# Microcontroller.net
KiCad netlist of a schematic drawn in Altium Designer
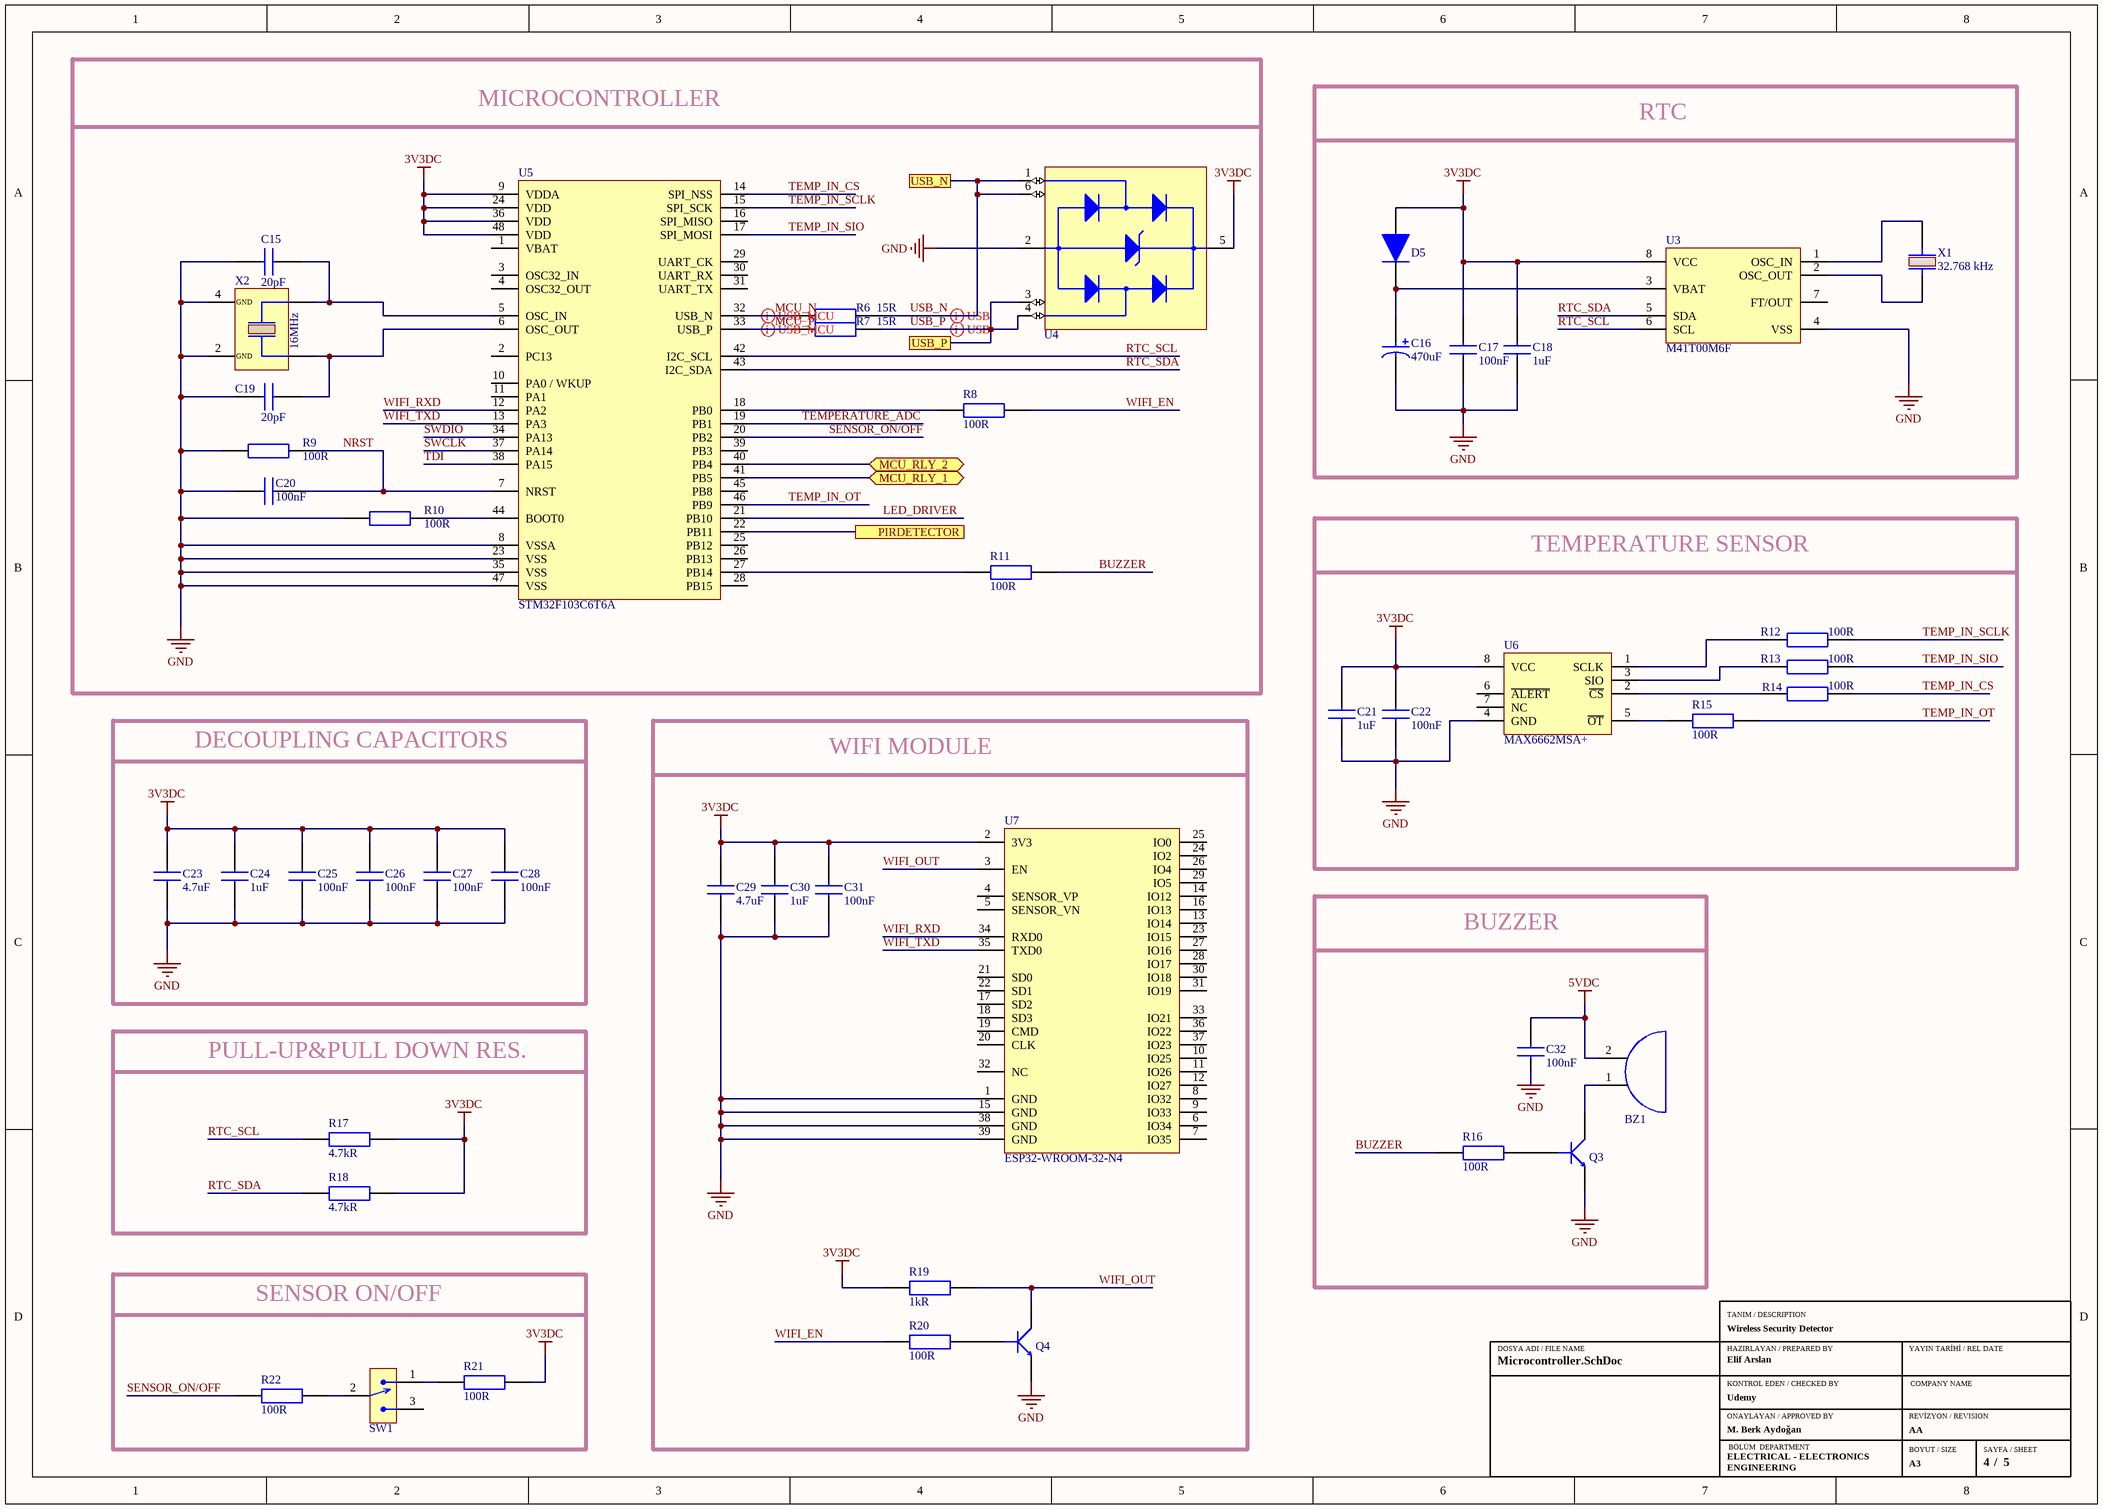
[diagram p0: Microcontroller.SchDoc]

(export (version "E")
  (design (tool "Eeschema 10.0.6"))
  (components
    (comp (ref "BZ1")
      (value "CMI-9605IC-0580T")
      (footprint "CMI-9605IC")
      (description "Audio Buzzer Magnetic 3VDC 7VDC 30mA 5VDC 85dB 2600Hz to 2800Hz Through Hole Pin Box")
      (fields (field (name "MANUFACTURER") "CUI Devices"))
      (libsource (lib "UDEMY_Library") (part "CMI-9605IC-0580T"))
    )
    (comp (ref "C15")
      (value "CL10C200JB8NNNC")
      (footprint "CAP_0603")
      (description "CAP CER 20pF %5 0603")
      (fields
        (field (name "MANUFACTURER") "Samsung")
        (field (name "TOLERANCE") "5%")
        (field (name "CAPACITANCE") "20pF")
      )
      (libsource (lib "UDEMY_Library") (part "CAP CER 20pF 0603"))
    )
    (comp (ref "C16")
      (value "ESH477M050AL3AA")
      (footprint "CAP_RADIAL_D10_P5")
      (description "CAP ALUM 470UF 20% 50V RADIAL")
      (fields
        (field (name "MANUFACTURER") "KEMET")
        (field (name "TOLERANCE") "20%")
        (field (name "CAPACITANCE") "470uF")
      )
      (libsource (lib "UDEMY_Library") (part "CAP ALU ELEC 470uF 50V"))
    )
    (comp (ref "C17")
      (value "CL21B104KBCNNNC")
      (footprint "CAP_0805")
      (description "CAP CER 0.1UF  %10 50V X7R  0805")
      (fields
        (field (name "MANUFACTURER") "Samsung")
        (field (name "TOLERANCE") "10%")
        (field (name "CAPACITANCE") "100nF")
      )
      (libsource (lib "UDEMY_Library") (part "CAP CER 100nF 0805"))
    )
    (comp (ref "C18")
      (value "CL21B105KBFNNNE")
      (footprint "CAP_0805")
      (description "CAP CER 1UF %10 50V 0805")
      (fields
        (field (name "MANUFACTURER") "Samsung")
        (field (name "TOLERANCE") "10%")
        (field (name "CAPACITANCE") "1uF")
      )
      (libsource (lib "UDEMY_Library") (part "CAP CER 1uF 0805"))
    )
    (comp (ref "C19")
      (value "CL10C200JB8NNNC")
      (footprint "CAP_0603")
      (description "CAP CER 20pF %5 0603")
      (fields
        (field (name "MANUFACTURER") "Samsung")
        (field (name "TOLERANCE") "5%")
        (field (name "CAPACITANCE") "20pF")
      )
      (libsource (lib "UDEMY_Library") (part "CAP CER 20pF 0603"))
    )
    (comp (ref "C20")
      (value "C0603C104K4RACTU")
      (footprint "CAP_0603")
      (description "CAP CER 100nF %10 0603 SMD")
      (fields
        (field (name "MANUFACTURER") "KEMET")
        (field (name "TOLERANCE") "10%")
        (field (name "CAPACITANCE") "100nF")
      )
      (libsource (lib "UDEMY_Library") (part "CAP CER 100nF 0603"))
    )
    (comp (ref "C21")
      (value "CL21B105KBFNNNE")
      (footprint "CAP_0805")
      (description "CAP CER 1UF %10 50V 0805")
      (fields
        (field (name "MANUFACTURER") "Samsung")
        (field (name "TOLERANCE") "10%")
        (field (name "CAPACITANCE") "1uF")
      )
      (libsource (lib "UDEMY_Library") (part "CAP CER 1uF 0805"))
    )
    (comp (ref "C22")
      (value "CL21B104KBCNNNC")
      (footprint "CAP_0805")
      (description "CAP CER 0.1UF  %10 50V X7R  0805")
      (fields
        (field (name "MANUFACTURER") "Samsung")
        (field (name "TOLERANCE") "10%")
        (field (name "CAPACITANCE") "100nF")
      )
      (libsource (lib "UDEMY_Library") (part "CAP CER 100nF 0805"))
    )
    (comp (ref "C23")
      (value "CL21A475KAQNNNE")
      (footprint "CAP_0805")
      (description "CAP CER 4.7UF 25V X5R %10 0805")
      (fields
        (field (name "MANUFACTURER") "Samsung")
        (field (name "TOLERANCE") "10%")
        (field (name "CAPACITANCE") "4.7uF")
      )
      (libsource (lib "UDEMY_Library") (part "CAP CER  4.7uF 0805"))
    )
    (comp (ref "C24")
      (value "CL21B105KBFNNNE")
      (footprint "CAP_0805")
      (description "CAP CER 1UF %10 50V 0805")
      (fields
        (field (name "MANUFACTURER") "Samsung")
        (field (name "TOLERANCE") "10%")
        (field (name "CAPACITANCE") "1uF")
      )
      (libsource (lib "UDEMY_Library") (part "CAP CER 1uF 0805"))
    )
    (comp (ref "C25")
      (value "C0603C104K4RACTU")
      (footprint "CAP_0603")
      (description "CAP CER 100nF %10 0603 SMD")
      (fields
        (field (name "MANUFACTURER") "KEMET")
        (field (name "TOLERANCE") "10%")
        (field (name "CAPACITANCE") "100nF")
      )
      (libsource (lib "UDEMY_Library") (part "CAP CER 100nF 0603"))
    )
    (comp (ref "C26")
      (value "C0603C104K4RACTU")
      (footprint "CAP_0603")
      (description "CAP CER 100nF %10 0603 SMD")
      (fields
        (field (name "MANUFACTURER") "KEMET")
        (field (name "TOLERANCE") "10%")
        (field (name "CAPACITANCE") "100nF")
      )
      (libsource (lib "UDEMY_Library") (part "CAP CER 100nF 0603"))
    )
    (comp (ref "C27")
      (value "C0603C104K4RACTU")
      (footprint "CAP_0603")
      (description "CAP CER 100nF %10 0603 SMD")
      (fields
        (field (name "MANUFACTURER") "KEMET")
        (field (name "TOLERANCE") "10%")
        (field (name "CAPACITANCE") "100nF")
      )
      (libsource (lib "UDEMY_Library") (part "CAP CER 100nF 0603"))
    )
    (comp (ref "C28")
      (value "C0603C104K4RACTU")
      (footprint "CAP_0603")
      (description "CAP CER 100nF %10 0603 SMD")
      (fields
        (field (name "MANUFACTURER") "KEMET")
        (field (name "TOLERANCE") "10%")
        (field (name "CAPACITANCE") "100nF")
      )
      (libsource (lib "UDEMY_Library") (part "CAP CER 100nF 0603"))
    )
    (comp (ref "C29")
      (value "CL21A475KAQNNNE")
      (footprint "CAP_0805")
      (description "CAP CER 4.7UF 25V X5R %10 0805")
      (fields
        (field (name "MANUFACTURER") "Samsung")
        (field (name "TOLERANCE") "10%")
        (field (name "CAPACITANCE") "4.7uF")
      )
      (libsource (lib "UDEMY_Library") (part "CAP CER  4.7uF 0805"))
    )
    (comp (ref "C30")
      (value "CL21B105KBFNNNE")
      (footprint "CAP_0805")
      (description "CAP CER 1UF %10 50V 0805")
      (fields
        (field (name "MANUFACTURER") "Samsung")
        (field (name "TOLERANCE") "10%")
        (field (name "CAPACITANCE") "1uF")
      )
      (libsource (lib "UDEMY_Library") (part "CAP CER 1uF 0805"))
    )
    (comp (ref "C31")
      (value "CL21B104KBCNNNC")
      (footprint "CAP_0805")
      (description "CAP CER 0.1UF  %10 50V X7R  0805")
      (fields
        (field (name "MANUFACTURER") "Samsung")
        (field (name "TOLERANCE") "10%")
        (field (name "CAPACITANCE") "100nF")
      )
      (libsource (lib "UDEMY_Library") (part "CAP CER 100nF 0805"))
    )
    (comp (ref "C32")
      (value "CL21B104KBCNNNC")
      (footprint "CAP_0805")
      (description "CAP CER 0.1UF  %10 50V X7R  0805")
      (fields
        (field (name "MANUFACTURER") "Samsung")
        (field (name "TOLERANCE") "10%")
        (field (name "CAPACITANCE") "100nF")
      )
      (libsource (lib "UDEMY_Library") (part "CAP CER 100nF 0805"))
    )
    (comp (ref "D5")
      (value "1N4148WS")
      (footprint "SOD323F")
      (description "VR=75V IF=150mA Trr=4ns P=200mW")
      (fields (field (name "MANUFACTURER") "ON Semiconductor / Fairchild"))
      (libsource (lib "UDEMY_Library") (part "1N4148WS"))
    )
    (comp (ref "Q3")
      (value "MMBT3904-7-F")
      (footprint "SOT-23F")
      (description "Bipolar (BJT) Transistor NPN 40 V 200 mA 300MHz 300 mW Surface Mount SOT-23-3")
      (fields (field (name "MANUFACTURER") "Diodes Zetex"))
      (libsource (lib "UDEMY_Library") (part "MMBT3904-7-F"))
    )
    (comp (ref "Q4")
      (value "MMBT3904-7-F")
      (footprint "SOT-23F")
      (description "Bipolar (BJT) Transistor NPN 40 V 200 mA 300MHz 300 mW Surface Mount SOT-23-3")
      (fields (field (name "MANUFACTURER") "Diodes Zetex"))
      (libsource (lib "UDEMY_Library") (part "MMBT3904-7-F"))
    )
    (comp (ref "R6")
      (value "RC0603JR-0715RL")
      (footprint "RES_0603")
      (description "RES 15 %5 OHM 0603 SMD")
      (fields
        (field (name "MANUFACTURER") "Yageo")
        (field (name "TOLERANCE") "5%")
        (field (name "RESISTANCE") "15R")
      )
      (libsource (lib "UDEMY_Library") (part "RES 15 OHM 0603"))
    )
    (comp (ref "R7")
      (value "RC0603JR-0715RL")
      (footprint "RES_0603")
      (description "RES 15 %5 OHM 0603 SMD")
      (fields
        (field (name "MANUFACTURER") "Yageo")
        (field (name "TOLERANCE") "5%")
        (field (name "RESISTANCE") "15R")
      )
      (libsource (lib "UDEMY_Library") (part "RES 15 OHM 0603"))
    )
    (comp (ref "R8")
      (value "RC0603JR-07100RL")
      (footprint "RES_0603")
      (description "RES 100 %5 OHM 0603 SMD")
      (fields
        (field (name "MANUFACTURER") "Yageo")
        (field (name "TOLERANCE") "5%")
        (field (name "RESISTANCE") "100R")
      )
      (libsource (lib "UDEMY_Library") (part "RES 100 OHM 0603"))
    )
    (comp (ref "R9")
      (value "RC0603JR-07100RL")
      (footprint "RES_0603")
      (description "RES 100 %5 OHM 0603 SMD")
      (fields
        (field (name "MANUFACTURER") "Yageo")
        (field (name "TOLERANCE") "5%")
        (field (name "RESISTANCE") "100R")
      )
      (libsource (lib "UDEMY_Library") (part "RES 100 OHM 0603"))
    )
    (comp (ref "R10")
      (value "RC0603JR-07100RL")
      (footprint "RES_0603")
      (description "RES 100 %5 OHM 0603 SMD")
      (fields
        (field (name "MANUFACTURER") "Yageo")
        (field (name "TOLERANCE") "5%")
        (field (name "RESISTANCE") "100R")
      )
      (libsource (lib "UDEMY_Library") (part "RES 100 OHM 0603"))
    )
    (comp (ref "R11")
      (value "RC0603JR-07100RL")
      (footprint "RES_0603")
      (description "RES 100 %5 OHM 0603 SMD")
      (fields
        (field (name "MANUFACTURER") "Yageo")
        (field (name "TOLERANCE") "5%")
        (field (name "RESISTANCE") "100R")
      )
      (libsource (lib "UDEMY_Library") (part "RES 100 OHM 0603"))
    )
    (comp (ref "R12")
      (value "RC0603JR-07100RL")
      (footprint "RES_0603")
      (description "RES 100 %5 OHM 0603 SMD")
      (fields
        (field (name "MANUFACTURER") "Yageo")
        (field (name "TOLERANCE") "5%")
        (field (name "RESISTANCE") "100R")
      )
      (libsource (lib "UDEMY_Library") (part "RES 100 OHM 0603"))
    )
    (comp (ref "R13")
      (value "RC0603JR-07100RL")
      (footprint "RES_0603")
      (description "RES 100 %5 OHM 0603 SMD")
      (fields
        (field (name "MANUFACTURER") "Yageo")
        (field (name "TOLERANCE") "5%")
        (field (name "RESISTANCE") "100R")
      )
      (libsource (lib "UDEMY_Library") (part "RES 100 OHM 0603"))
    )
    (comp (ref "R14")
      (value "RC0603JR-07100RL")
      (footprint "RES_0603")
      (description "RES 100 %5 OHM 0603 SMD")
      (fields
        (field (name "MANUFACTURER") "Yageo")
        (field (name "TOLERANCE") "5%")
        (field (name "RESISTANCE") "100R")
      )
      (libsource (lib "UDEMY_Library") (part "RES 100 OHM 0603"))
    )
    (comp (ref "R15")
      (value "RC0603JR-07100RL")
      (footprint "RES_0603")
      (description "RES 100 %5 OHM 0603 SMD")
      (fields
        (field (name "MANUFACTURER") "Yageo")
        (field (name "TOLERANCE") "5%")
        (field (name "RESISTANCE") "100R")
      )
      (libsource (lib "UDEMY_Library") (part "RES 100 OHM 0603"))
    )
    (comp (ref "R16")
      (value "RC0603JR-07100RL")
      (footprint "RES_0603")
      (description "RES 100 %5 OHM 0603 SMD")
      (fields
        (field (name "MANUFACTURER") "Yageo")
        (field (name "TOLERANCE") "5%")
        (field (name "RESISTANCE") "100R")
      )
      (libsource (lib "UDEMY_Library") (part "RES 100 OHM 0603"))
    )
    (comp (ref "R17")
      (value "RC0603JR-074K7L")
      (footprint "RES_0603")
      (description "RES 4.7K OHM %5 0603 SMD")
      (fields
        (field (name "MANUFACTURER") "Yageo")
        (field (name "TOLERANCE") "5%")
        (field (name "RESISTANCE") "4.7kR")
      )
      (libsource (lib "UDEMY_Library") (part "RES 4.7K OHM 0603"))
    )
    (comp (ref "R18")
      (value "RC0603JR-074K7L")
      (footprint "RES_0603")
      (description "RES 4.7K OHM %5 0603 SMD")
      (fields
        (field (name "MANUFACTURER") "Yageo")
        (field (name "TOLERANCE") "5%")
        (field (name "RESISTANCE") "4.7kR")
      )
      (libsource (lib "UDEMY_Library") (part "RES 4.7K OHM 0603"))
    )
    (comp (ref "R19")
      (value "RC0603FR-071KL")
      (footprint "RES_0603")
      (description "RES SMD 1K OHM %1 0603")
      (fields
        (field (name "MANUFACTURER") "Yageo")
        (field (name "TOLERANCE") "1%")
        (field (name "RESISTANCE") "1kR")
      )
      (libsource (lib "UDEMY_Library") (part "RES 1K OHM 0603"))
    )
    (comp (ref "R20")
      (value "RC0603JR-07100RL")
      (footprint "RES_0603")
      (description "RES 100 %5 OHM 0603 SMD")
      (fields
        (field (name "MANUFACTURER") "Yageo")
        (field (name "TOLERANCE") "5%")
        (field (name "RESISTANCE") "100R")
      )
      (libsource (lib "UDEMY_Library") (part "RES 100 OHM 0603"))
    )
    (comp (ref "R21")
      (value "RC0603JR-07100RL")
      (footprint "RES_0603")
      (description "RES 100 %5 OHM 0603 SMD")
      (fields
        (field (name "MANUFACTURER") "Yageo")
        (field (name "TOLERANCE") "5%")
        (field (name "RESISTANCE") "100R")
      )
      (libsource (lib "UDEMY_Library") (part "RES 100 OHM 0603"))
    )
    (comp (ref "R22")
      (value "RC0603JR-07100RL")
      (footprint "RES_0603")
      (description "RES 100 %5 OHM 0603 SMD")
      (fields
        (field (name "MANUFACTURER") "Yageo")
        (field (name "TOLERANCE") "5%")
        (field (name "RESISTANCE") "100R")
      )
      (libsource (lib "UDEMY_Library") (part "RES 100 OHM 0603"))
    )
    (comp (ref "SW1")
      (value "EG1215AA")
      (footprint "EG1215AA")
      (description "Slide Switch, SPDT, 0.025A, 24V, SMD")
      (fields (field (name "MANUFACTURER") "E-Switch") (field (name "TOLERANCE") "4.95%"))
      (libsource (lib "UDEMY_Library") (part "EG1215AA"))
    )
    (comp (ref "U3")
      (value "M41T00M6F")
      (footprint "SOIC8")
      (description "IC RTC CLK/CALENDAR I2C 8-SOIC")
      (fields (field (name "MANUFACTURER") "STMicroelectronics"))
      (libsource (lib "UDEMY_Library") (part "M41T00"))
    )
    (comp (ref "U4")
      (value "USBLC6-2SC6")
      (footprint "SOT-23-6L")
      (description "TVS DIODE 5.25VWM 17VC SOT23-6")
      (fields (field (name "MANUFACTURER") "STMicroelectronics"))
      (libsource (lib "UDEMY_Library") (part "USB PROTECTION"))
    )
    (comp (ref "U5")
      (value "STM32F103C6T6A")
      (footprint "LQFP-48")
      (description "MCU 32-bit STM32F ARM Cortex M3 RISC 32KB Flash 2.5V/3.3V 48-Pin LQFP Tray")
      (fields (field (name "MANUFACTURER") "STMicroelectronics") (field (name "DESIGNED BY") "ELİF"))
      (libsource (lib "UDEMY_Library") (part "STM32F103C6T6A"))
    )
    (comp (ref "U6")
      (value "MAX6662MSA+")
      (footprint "SOIC8")
      (description "Temp Sensor Digital Serial (3-Wire, SPI) 8-Pin SOIC N Tube")
      (fields (field (name "MANUFACTURER") "Maxim"))
      (libsource (lib "UDEMY_Library") (part "MAX6662"))
    )
    (comp (ref "U7")
      (value "ESP32-WROOM-32-N4")
      (footprint "ESP32-32E")
      (description "Rx Txrx Mod Wifi Surface Mount")
      (fields (field (name "MANUFACTURER") "Espressif Systems"))
      (libsource (lib "UDEMY_Library") (part "ESP32-WROOM-32-N4"))
    )
    (comp (ref "X1")
      (value "ABS05-32.768KHZ-T")
      (footprint "ABS05")
      (description "Crystal, 32.768 kHz, SMD, 1.6mm x 1mm, 12.5 pF, 20 ppm, ABS05 Series")
      (fields
        (field (name "MANUFACTURER") "Abracon")
        (field (name "TOLERANCE") "20ppm")
        (field (name "OPERATING FREQUENCY") "32.768 kHz")
      )
      (libsource (lib "UDEMY_Library") (part "CRYSTAL 32758kHZ"))
    )
    (comp (ref "X2")
      (value "ECS-160-20-30B-TR")
      (footprint "ECS")
      (description "16 MHz ±30ppm Crystal 20pF 50 Ohms 4-SMD, No Lead")
      (fields
        (field (name "MANUFACTURER") "ECS International")
        (field (name "TOLERANCE") "50ppm")
        (field (name "FREQUENCY") "16MHz")
      )
      (libsource (lib "UDEMY_Library") (part "CRYSTAL 16MHZ"))
    )
  )
  (nets
    (net (code "1") (name "/BUZZER") (class "Default")
      (node (ref "R11") (pin "2") (pinfunction "2_2") (pintype "passive"))
      (node (ref "R16") (pin "1") (pinfunction "1_1") (pintype "passive"))
    )
    (net (code "2") (name "/LED_DRIVER") (class "Default")
      (node (ref "U5") (pin "21") (pinfunction "PB10_21") (pintype "passive"))
    )
    (net (code "3") (name "/MCU_N") (class "Default")
      (node (ref "R6") (pin "1") (pinfunction "1_1") (pintype "passive"))
      (node (ref "U5") (pin "32") (pinfunction "USB_N_32") (pintype "passive"))
    )
    (net (code "4") (name "/MCU_P") (class "Default")
      (node (ref "R7") (pin "1") (pinfunction "1_1") (pintype "passive"))
      (node (ref "U5") (pin "33") (pinfunction "USB_P_33") (pintype "passive"))
    )
    (net (code "5") (name "/MCU_RLY_1") (class "Default")
      (node (ref "U5") (pin "41") (pinfunction "PB5_41") (pintype "passive"))
    )
    (net (code "6") (name "/MCU_RLY_2") (class "Default")
      (node (ref "U5") (pin "40") (pinfunction "PB4_40") (pintype "passive"))
    )
    (net (code "7") (name "/NRST") (class "Default")
      (node (ref "C20") (pin "1") (pinfunction "1_1") (pintype "passive"))
      (node (ref "R9") (pin "2") (pinfunction "2_2") (pintype "passive"))
      (node (ref "U5") (pin "7") (pinfunction "NRST_7") (pintype "passive"))
    )
    (net (code "8") (name "/PIRDETECTOR") (class "Default")
      (node (ref "U5") (pin "22") (pinfunction "PB11_22") (pintype "passive"))
    )
    (net (code "9") (name "/RTC_SCL") (class "Default")
      (node (ref "R17") (pin "1") (pinfunction "1_1") (pintype "passive"))
      (node (ref "U3") (pin "6") (pinfunction "SCL_6") (pintype "passive"))
      (node (ref "U5") (pin "42") (pinfunction "I2C_SCL_42") (pintype "passive"))
    )
    (net (code "10") (name "/RTC_SDA") (class "Default")
      (node (ref "R18") (pin "1") (pinfunction "1_1") (pintype "passive"))
      (node (ref "U3") (pin "5") (pinfunction "SDA_5") (pintype "passive"))
      (node (ref "U5") (pin "43") (pinfunction "I2C_SDA_43") (pintype "passive"))
    )
    (net (code "11") (name "/SENSOR_ON{slash}OFF") (class "Default")
      (node (ref "R22") (pin "2") (pinfunction "2_2") (pintype "passive"))
      (node (ref "U5") (pin "20") (pinfunction "PB2_20") (pintype "passive"))
    )
    (net (code "12") (name "/SWCLK") (class "Default")
      (node (ref "U5") (pin "37") (pinfunction "PA14_37") (pintype "passive"))
    )
    (net (code "13") (name "/SWDIO") (class "Default")
      (node (ref "U5") (pin "34") (pinfunction "PA13_34") (pintype "passive"))
    )
    (net (code "14") (name "/TDI") (class "Default")
      (node (ref "U5") (pin "38") (pinfunction "PA15_38") (pintype "passive"))
    )
    (net (code "15") (name "/TEMPERATURE_ADC") (class "Default")
      (node (ref "U5") (pin "19") (pinfunction "PB1_19") (pintype "passive"))
    )
    (net (code "16") (name "/TEMP_IN_CS") (class "Default")
      (node (ref "R14") (pin "2") (pinfunction "2_2") (pintype "passive"))
      (node (ref "U5") (pin "14") (pinfunction "SPI_NSS_14") (pintype "passive"))
    )
    (net (code "17") (name "/TEMP_IN_OT") (class "Default")
      (node (ref "R15") (pin "2") (pinfunction "2_2") (pintype "passive"))
      (node (ref "U5") (pin "46") (pinfunction "PB9_46") (pintype "passive"))
    )
    (net (code "18") (name "/TEMP_IN_SCLK") (class "Default")
      (node (ref "R12") (pin "2") (pinfunction "2_2") (pintype "passive"))
      (node (ref "U5") (pin "15") (pinfunction "SPI_SCK_15") (pintype "passive"))
    )
    (net (code "19") (name "/TEMP_IN_SIO") (class "Default")
      (node (ref "R13") (pin "2") (pinfunction "2_2") (pintype "passive"))
      (node (ref "U5") (pin "17") (pinfunction "SPI_MOSI_17") (pintype "passive"))
    )
    (net (code "20") (name "/USB_N") (class "Default")
      (node (ref "R6") (pin "2") (pinfunction "2_2") (pintype "passive"))
      (node (ref "U4") (pin "1") (pinfunction "I/O1_IN_1") (pintype "bidirectional"))
      (node (ref "U4") (pin "6") (pinfunction "I/O1_OUT_6") (pintype "bidirectional"))
    )
    (net (code "21") (name "/USB_P") (class "Default")
      (node (ref "R7") (pin "2") (pinfunction "2_2") (pintype "passive"))
      (node (ref "U4") (pin "3") (pinfunction "I/O2_IN_3") (pintype "bidirectional"))
      (node (ref "U4") (pin "4") (pinfunction "I/O2_OUT_4") (pintype "bidirectional"))
    )
    (net (code "22") (name "/WIFI_EN") (class "Default")
      (node (ref "R20") (pin "1") (pinfunction "1_1") (pintype "passive"))
      (node (ref "R8") (pin "2") (pinfunction "2_2") (pintype "passive"))
    )
    (net (code "23") (name "/WIFI_OUT") (class "Default")
      (node (ref "Q4") (pin "3") (pinfunction "C_3") (pintype "passive"))
      (node (ref "R19") (pin "2") (pinfunction "2_2") (pintype "passive"))
      (node (ref "U7") (pin "3") (pinfunction "EN_3") (pintype "passive"))
    )
    (net (code "24") (name "/WIFI_RXD") (class "Default")
      (node (ref "U5") (pin "12") (pinfunction "PA2_12") (pintype "passive"))
      (node (ref "U7") (pin "34") (pinfunction "RXD0_34") (pintype "passive"))
    )
    (net (code "25") (name "/WIFI_TXD") (class "Default")
      (node (ref "U5") (pin "13") (pinfunction "PA3_13") (pintype "passive"))
      (node (ref "U7") (pin "35") (pinfunction "TXD0_35") (pintype "passive"))
    )
    (net (code "26") (name "3V3DC") (class "Default")
      (node (ref "C17") (pin "2") (pinfunction "2_2") (pintype "passive"))
      (node (ref "C18") (pin "2") (pinfunction "2_2") (pintype "passive"))
      (node (ref "C21") (pin "2") (pinfunction "2_2") (pintype "passive"))
      (node (ref "C22") (pin "2") (pinfunction "2_2") (pintype "passive"))
      (node (ref "C23") (pin "2") (pinfunction "2_2") (pintype "passive"))
      (node (ref "C24") (pin "2") (pinfunction "2_2") (pintype "passive"))
      (node (ref "C25") (pin "2") (pinfunction "2_2") (pintype "passive"))
      (node (ref "C26") (pin "2") (pinfunction "2_2") (pintype "passive"))
      (node (ref "C27") (pin "2") (pinfunction "2_2") (pintype "passive"))
      (node (ref "C28") (pin "2") (pinfunction "2_2") (pintype "passive"))
      (node (ref "C29") (pin "2") (pinfunction "2_2") (pintype "passive"))
      (node (ref "C30") (pin "2") (pinfunction "2_2") (pintype "passive"))
      (node (ref "C31") (pin "2") (pinfunction "2_2") (pintype "passive"))
      (node (ref "D5") (pin "2") (pinfunction "2_2") (pintype "passive"))
      (node (ref "R17") (pin "2") (pinfunction "2_2") (pintype "passive"))
      (node (ref "R18") (pin "2") (pinfunction "2_2") (pintype "passive"))
      (node (ref "R19") (pin "1") (pinfunction "1_1") (pintype "passive"))
      (node (ref "R21") (pin "2") (pinfunction "2_2") (pintype "passive"))
      (node (ref "U3") (pin "8") (pinfunction "VCC_8") (pintype "passive"))
      (node (ref "U4") (pin "5") (pinfunction "VBUS_5") (pintype "power_in"))
      (node (ref "U5") (pin "24") (pinfunction "VDD_24") (pintype "passive"))
      (node (ref "U5") (pin "36") (pinfunction "VDD_36") (pintype "passive"))
      (node (ref "U5") (pin "48") (pinfunction "VDD_48") (pintype "passive"))
      (node (ref "U5") (pin "9") (pinfunction "VDDA_9") (pintype "passive"))
      (node (ref "U6") (pin "8") (pinfunction "VCC_8") (pintype "passive"))
      (node (ref "U7") (pin "2") (pinfunction "3V3_2") (pintype "passive"))
    )
    (net (code "27") (name "5VDC") (class "Default")
      (node (ref "BZ1") (pin "2") (pinfunction "2_2") (pintype "passive"))
      (node (ref "C32") (pin "1") (pinfunction "1_1") (pintype "passive"))
    )
    (net (code "28") (name "GND") (class "Default")
      (node (ref "C15") (pin "2") (pinfunction "2_2") (pintype "passive"))
      (node (ref "C16") (pin "2") (pinfunction "2_2") (pintype "passive"))
      (node (ref "C17") (pin "1") (pinfunction "1_1") (pintype "passive"))
      (node (ref "C18") (pin "1") (pinfunction "1_1") (pintype "passive"))
      (node (ref "C19") (pin "1") (pinfunction "1_1") (pintype "passive"))
      (node (ref "C20") (pin "2") (pinfunction "2_2") (pintype "passive"))
      (node (ref "C21") (pin "1") (pinfunction "1_1") (pintype "passive"))
      (node (ref "C22") (pin "1") (pinfunction "1_1") (pintype "passive"))
      (node (ref "C23") (pin "1") (pinfunction "1_1") (pintype "passive"))
      (node (ref "C24") (pin "1") (pinfunction "1_1") (pintype "passive"))
      (node (ref "C25") (pin "1") (pinfunction "1_1") (pintype "passive"))
      (node (ref "C26") (pin "1") (pinfunction "1_1") (pintype "passive"))
      (node (ref "C27") (pin "1") (pinfunction "1_1") (pintype "passive"))
      (node (ref "C28") (pin "1") (pinfunction "1_1") (pintype "passive"))
      (node (ref "C29") (pin "1") (pinfunction "1_1") (pintype "passive"))
      (node (ref "C30") (pin "1") (pinfunction "1_1") (pintype "passive"))
      (node (ref "C31") (pin "1") (pinfunction "1_1") (pintype "passive"))
      (node (ref "C32") (pin "2") (pinfunction "2_2") (pintype "passive"))
      (node (ref "Q3") (pin "2") (pinfunction "E_2") (pintype "passive"))
      (node (ref "Q4") (pin "2") (pinfunction "E_2") (pintype "passive"))
      (node (ref "R10") (pin "1") (pinfunction "1_1") (pintype "passive"))
      (node (ref "R9") (pin "1") (pinfunction "1_1") (pintype "passive"))
      (node (ref "U3") (pin "4") (pinfunction "VSS_4") (pintype "passive"))
      (node (ref "U4") (pin "2") (pinfunction "GND_2") (pintype "power_in"))
      (node (ref "U5") (pin "23") (pinfunction "VSS_23") (pintype "passive"))
      (node (ref "U5") (pin "35") (pinfunction "VSS_35") (pintype "passive"))
      (node (ref "U5") (pin "47") (pinfunction "VSS_47") (pintype "passive"))
      (node (ref "U5") (pin "8") (pinfunction "VSSA_8") (pintype "passive"))
      (node (ref "U6") (pin "4") (pinfunction "GND_4") (pintype "passive"))
      (node (ref "U7") (pin "1") (pinfunction "GND_1") (pintype "passive"))
      (node (ref "U7") (pin "15") (pinfunction "GND_15") (pintype "passive"))
      (node (ref "U7") (pin "38") (pinfunction "GND_38") (pintype "passive"))
      (node (ref "U7") (pin "39") (pinfunction "GND_39") (pintype "passive"))
      (node (ref "X2") (pin "2") (pinfunction "GND_2") (pintype "passive"))
      (node (ref "X2") (pin "4") (pinfunction "GND_4") (pintype "passive"))
    )
    (net (code "29") (name "Net-(Q3-B)") (class "Default")
      (node (ref "Q3") (pin "1") (pinfunction "B_1") (pintype "passive"))
      (node (ref "R16") (pin "2") (pinfunction "2_2") (pintype "passive"))
    )
    (net (code "30") (name "Net-(Q3-C)") (class "Default")
      (node (ref "BZ1") (pin "1") (pinfunction "1_1") (pintype "passive"))
      (node (ref "Q3") (pin "3") (pinfunction "C_3") (pintype "passive"))
    )
    (net (code "31") (name "Net-(Q4-B)") (class "Default")
      (node (ref "Q4") (pin "1") (pinfunction "B_1") (pintype "passive"))
      (node (ref "R20") (pin "2") (pinfunction "2_2") (pintype "passive"))
    )
    (net (code "32") (name "Net-(R21-Pad1)") (class "Default")
      (node (ref "R21") (pin "1") (pinfunction "1_1") (pintype "passive"))
      (node (ref "SW1") (pin "1") (pinfunction "1_1") (pintype "passive"))
    )
    (net (code "33") (name "Net-(R22-Pad1)") (class "Default")
      (node (ref "R22") (pin "1") (pinfunction "1_1") (pintype "passive"))
      (node (ref "SW1") (pin "2") (pinfunction "2_2") (pintype "passive"))
    )
    (net (code "34") (name "Net-(U3-OSC_IN)") (class "Default")
      (node (ref "U3") (pin "1") (pinfunction "OSC_IN_1") (pintype "passive"))
      (node (ref "X1") (pin "2") (pinfunction "2_2") (pintype "passive"))
    )
    (net (code "35") (name "Net-(U3-OSC_OUT)") (class "Default")
      (node (ref "U3") (pin "2") (pinfunction "OSC_OUT_2") (pintype "passive"))
      (node (ref "X1") (pin "1") (pinfunction "1_1") (pintype "passive"))
    )
    (net (code "36") (name "Net-(U3-VBAT)") (class "Default")
      (node (ref "C16") (pin "1") (pinfunction "1_1") (pintype "passive"))
      (node (ref "D5") (pin "1") (pinfunction "1_1") (pintype "passive"))
      (node (ref "U3") (pin "3") (pinfunction "VBAT_3") (pintype "passive"))
    )
    (net (code "37") (name "Net-(U5-BOOT0)") (class "Default")
      (node (ref "R10") (pin "2") (pinfunction "2_2") (pintype "passive"))
      (node (ref "U5") (pin "44") (pinfunction "BOOT0_44") (pintype "passive"))
    )
    (net (code "38") (name "Net-(U5-OSC_IN)") (class "Default")
      (node (ref "C15") (pin "1") (pinfunction "1_1") (pintype "passive"))
      (node (ref "U5") (pin "5") (pinfunction "OSC_IN_5") (pintype "passive"))
      (node (ref "X2") (pin "3") (pinfunction "3_3") (pintype "passive"))
    )
    (net (code "39") (name "Net-(U5-OSC_OUT)") (class "Default")
      (node (ref "C19") (pin "2") (pinfunction "2_2") (pintype "passive"))
      (node (ref "U5") (pin "6") (pinfunction "OSC_OUT_6") (pintype "passive"))
      (node (ref "X2") (pin "1") (pinfunction "1_1") (pintype "passive"))
    )
    (net (code "40") (name "Net-(U5-PB0)") (class "Default")
      (node (ref "R8") (pin "1") (pinfunction "1_1") (pintype "passive"))
      (node (ref "U5") (pin "18") (pinfunction "PB0_18") (pintype "passive"))
    )
    (net (code "41") (name "Net-(U5-PB14)") (class "Default")
      (node (ref "R11") (pin "1") (pinfunction "1_1") (pintype "passive"))
      (node (ref "U5") (pin "27") (pinfunction "PB14_27") (pintype "passive"))
    )
    (net (code "42") (name "Net-(U6-SCLK)") (class "Default")
      (node (ref "R12") (pin "1") (pinfunction "1_1") (pintype "passive"))
      (node (ref "U6") (pin "1") (pinfunction "SCLK_1") (pintype "passive"))
    )
    (net (code "43") (name "Net-(U6-SIO)") (class "Default")
      (node (ref "R13") (pin "1") (pinfunction "1_1") (pintype "passive"))
      (node (ref "U6") (pin "3") (pinfunction "SIO_3") (pintype "passive"))
    )
    (net (code "44") (name "Net-(U6-~{CS})") (class "Default")
      (node (ref "R14") (pin "1") (pinfunction "1_1") (pintype "passive"))
      (node (ref "U6") (pin "2") (pinfunction "~{CS}_2") (pintype "passive"))
    )
    (net (code "45") (name "Net-(U6-~{OT})") (class "Default")
      (node (ref "R15") (pin "1") (pinfunction "1_1") (pintype "passive"))
      (node (ref "U6") (pin "5") (pinfunction "~{OT}_5") (pintype "passive"))
    )
    (net (code "46") (name "unconnected-(SW1-Pad3)") (class "Default")
      (node (ref "SW1") (pin "3") (pinfunction "3_3") (pintype "passive"))
    )
    (net (code "47") (name "unconnected-(U3-FT{slash}OUT-Pad7)") (class "Default")
      (node (ref "U3") (pin "7") (pinfunction "FT/OUT_7") (pintype "passive"))
    )
    (net (code "48") (name "unconnected-(U5-OSC32_IN-Pad3)") (class "Default")
      (node (ref "U5") (pin "3") (pinfunction "OSC32_IN_3") (pintype "passive"))
    )
    (net (code "49") (name "unconnected-(U5-OSC32_OUT-Pad4)") (class "Default")
      (node (ref "U5") (pin "4") (pinfunction "OSC32_OUT_4") (pintype "passive"))
    )
    (net (code "50") (name "unconnected-(U5-PA0_{slash}_WKUP-Pad10)") (class "Default")
      (node (ref "U5") (pin "10") (pinfunction "PA0_/_WKUP_10") (pintype "passive"))
    )
    (net (code "51") (name "unconnected-(U5-PA1-Pad11)") (class "Default")
      (node (ref "U5") (pin "11") (pinfunction "PA1_11") (pintype "passive"))
    )
    (net (code "52") (name "unconnected-(U5-PB3-Pad39)") (class "Default")
      (node (ref "U5") (pin "39") (pinfunction "PB3_39") (pintype "passive"))
    )
    (net (code "53") (name "unconnected-(U5-PB8-Pad45)") (class "Default")
      (node (ref "U5") (pin "45") (pinfunction "PB8_45") (pintype "passive"))
    )
    (net (code "54") (name "unconnected-(U5-PB12-Pad25)") (class "Default")
      (node (ref "U5") (pin "25") (pinfunction "PB12_25") (pintype "passive"))
    )
    (net (code "55") (name "unconnected-(U5-PB13-Pad26)") (class "Default")
      (node (ref "U5") (pin "26") (pinfunction "PB13_26") (pintype "passive"))
    )
    (net (code "56") (name "unconnected-(U5-PB15-Pad28)") (class "Default")
      (node (ref "U5") (pin "28") (pinfunction "PB15_28") (pintype "passive"))
    )
    (net (code "57") (name "unconnected-(U5-PC13-Pad2)") (class "Default")
      (node (ref "U5") (pin "2") (pinfunction "PC13_2") (pintype "passive"))
    )
    (net (code "58") (name "unconnected-(U5-SPI_MISO-Pad16)") (class "Default")
      (node (ref "U5") (pin "16") (pinfunction "SPI_MISO_16") (pintype "passive"))
    )
    (net (code "59") (name "unconnected-(U5-UART_CK-Pad29)") (class "Default")
      (node (ref "U5") (pin "29") (pinfunction "UART_CK_29") (pintype "passive"))
    )
    (net (code "60") (name "unconnected-(U5-UART_RX-Pad30)") (class "Default")
      (node (ref "U5") (pin "30") (pinfunction "UART_RX_30") (pintype "passive"))
    )
    (net (code "61") (name "unconnected-(U5-UART_TX-Pad31)") (class "Default")
      (node (ref "U5") (pin "31") (pinfunction "UART_TX_31") (pintype "passive"))
    )
    (net (code "62") (name "unconnected-(U5-VBAT-Pad1)") (class "Default")
      (node (ref "U5") (pin "1") (pinfunction "VBAT_1") (pintype "passive"))
    )
    (net (code "63") (name "unconnected-(U6-NC-Pad7)") (class "Default")
      (node (ref "U6") (pin "7") (pinfunction "NC_7") (pintype "passive"))
    )
    (net (code "64") (name "unconnected-(U6-~{ALERT}-Pad6)") (class "Default")
      (node (ref "U6") (pin "6") (pinfunction "~{ALERT}_6") (pintype "passive"))
    )
    (net (code "65") (name "unconnected-(U7-CLK-Pad20)") (class "Default")
      (node (ref "U7") (pin "20") (pinfunction "CLK_20") (pintype "passive"))
    )
    (net (code "66") (name "unconnected-(U7-CMD-Pad19)") (class "Default")
      (node (ref "U7") (pin "19") (pinfunction "CMD_19") (pintype "passive"))
    )
    (net (code "67") (name "unconnected-(U7-IO0-Pad25)") (class "Default")
      (node (ref "U7") (pin "25") (pinfunction "IO0_25") (pintype "passive"))
    )
    (net (code "68") (name "unconnected-(U7-IO2-Pad24)") (class "Default")
      (node (ref "U7") (pin "24") (pinfunction "IO2_24") (pintype "passive"))
    )
    (net (code "69") (name "unconnected-(U7-IO4-Pad26)") (class "Default")
      (node (ref "U7") (pin "26") (pinfunction "IO4_26") (pintype "passive"))
    )
    (net (code "70") (name "unconnected-(U7-IO5-Pad29)") (class "Default")
      (node (ref "U7") (pin "29") (pinfunction "IO5_29") (pintype "passive"))
    )
    (net (code "71") (name "unconnected-(U7-IO12-Pad14)") (class "Default")
      (node (ref "U7") (pin "14") (pinfunction "IO12_14") (pintype "passive"))
    )
    (net (code "72") (name "unconnected-(U7-IO13-Pad16)") (class "Default")
      (node (ref "U7") (pin "16") (pinfunction "IO13_16") (pintype "passive"))
    )
    (net (code "73") (name "unconnected-(U7-IO14-Pad13)") (class "Default")
      (node (ref "U7") (pin "13") (pinfunction "IO14_13") (pintype "passive"))
    )
    (net (code "74") (name "unconnected-(U7-IO15-Pad23)") (class "Default")
      (node (ref "U7") (pin "23") (pinfunction "IO15_23") (pintype "passive"))
    )
    (net (code "75") (name "unconnected-(U7-IO16-Pad27)") (class "Default")
      (node (ref "U7") (pin "27") (pinfunction "IO16_27") (pintype "passive"))
    )
    (net (code "76") (name "unconnected-(U7-IO17-Pad28)") (class "Default")
      (node (ref "U7") (pin "28") (pinfunction "IO17_28") (pintype "passive"))
    )
    (net (code "77") (name "unconnected-(U7-IO18-Pad30)") (class "Default")
      (node (ref "U7") (pin "30") (pinfunction "IO18_30") (pintype "passive"))
    )
    (net (code "78") (name "unconnected-(U7-IO19-Pad31)") (class "Default")
      (node (ref "U7") (pin "31") (pinfunction "IO19_31") (pintype "passive"))
    )
    (net (code "79") (name "unconnected-(U7-IO21-Pad33)") (class "Default")
      (node (ref "U7") (pin "33") (pinfunction "IO21_33") (pintype "passive"))
    )
    (net (code "80") (name "unconnected-(U7-IO22-Pad36)") (class "Default")
      (node (ref "U7") (pin "36") (pinfunction "IO22_36") (pintype "passive"))
    )
    (net (code "81") (name "unconnected-(U7-IO23-Pad37)") (class "Default")
      (node (ref "U7") (pin "37") (pinfunction "IO23_37") (pintype "passive"))
    )
    (net (code "82") (name "unconnected-(U7-IO25-Pad10)") (class "Default")
      (node (ref "U7") (pin "10") (pinfunction "IO25_10") (pintype "passive"))
    )
    (net (code "83") (name "unconnected-(U7-IO26-Pad11)") (class "Default")
      (node (ref "U7") (pin "11") (pinfunction "IO26_11") (pintype "passive"))
    )
    (net (code "84") (name "unconnected-(U7-IO27-Pad12)") (class "Default")
      (node (ref "U7") (pin "12") (pinfunction "IO27_12") (pintype "passive"))
    )
    (net (code "85") (name "unconnected-(U7-IO32-Pad8)") (class "Default")
      (node (ref "U7") (pin "8") (pinfunction "IO32_8") (pintype "passive"))
    )
    (net (code "86") (name "unconnected-(U7-IO33-Pad9)") (class "Default")
      (node (ref "U7") (pin "9") (pinfunction "IO33_9") (pintype "passive"))
    )
    (net (code "87") (name "unconnected-(U7-IO34-Pad6)") (class "Default")
      (node (ref "U7") (pin "6") (pinfunction "IO34_6") (pintype "passive"))
    )
    (net (code "88") (name "unconnected-(U7-IO35-Pad7)") (class "Default")
      (node (ref "U7") (pin "7") (pinfunction "IO35_7") (pintype "passive"))
    )
    (net (code "89") (name "unconnected-(U7-NC-Pad32)") (class "Default")
      (node (ref "U7") (pin "32") (pinfunction "NC_32") (pintype "passive"))
    )
    (net (code "90") (name "unconnected-(U7-SD0-Pad21)") (class "Default")
      (node (ref "U7") (pin "21") (pinfunction "SD0_21") (pintype "passive"))
    )
    (net (code "91") (name "unconnected-(U7-SD1-Pad22)") (class "Default")
      (node (ref "U7") (pin "22") (pinfunction "SD1_22") (pintype "passive"))
    )
    (net (code "92") (name "unconnected-(U7-SD2-Pad17)") (class "Default")
      (node (ref "U7") (pin "17") (pinfunction "SD2_17") (pintype "passive"))
    )
    (net (code "93") (name "unconnected-(U7-SD3-Pad18)") (class "Default")
      (node (ref "U7") (pin "18") (pinfunction "SD3_18") (pintype "passive"))
    )
    (net (code "94") (name "unconnected-(U7-SENSOR_VN-Pad5)") (class "Default")
      (node (ref "U7") (pin "5") (pinfunction "SENSOR_VN_5") (pintype "passive"))
    )
    (net (code "95") (name "unconnected-(U7-SENSOR_VP-Pad4)") (class "Default")
      (node (ref "U7") (pin "4") (pinfunction "SENSOR_VP_4") (pintype "passive"))
    )
  )
)
